# powerblade_5v0.net
KiCad netlist of a schematic drawn in EAGLE
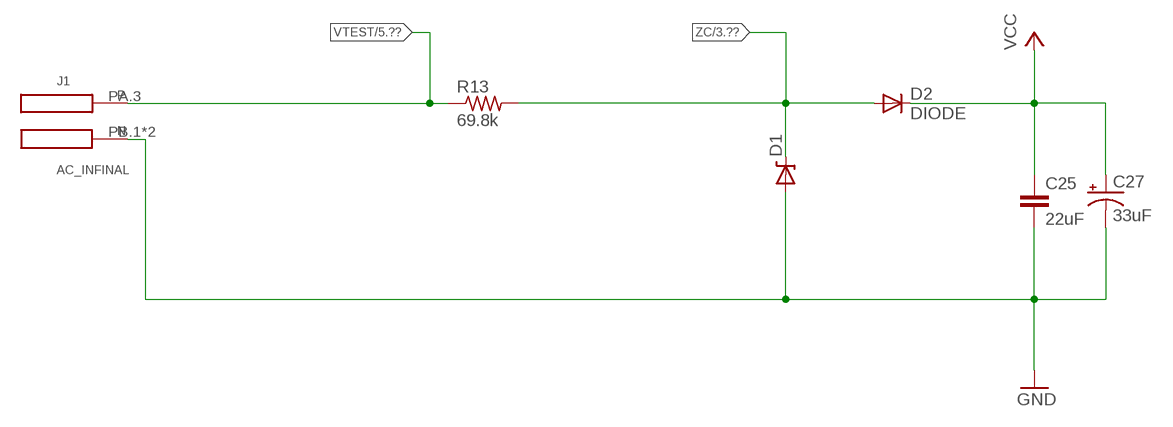
[diagram p0: schematic, sheet 1]
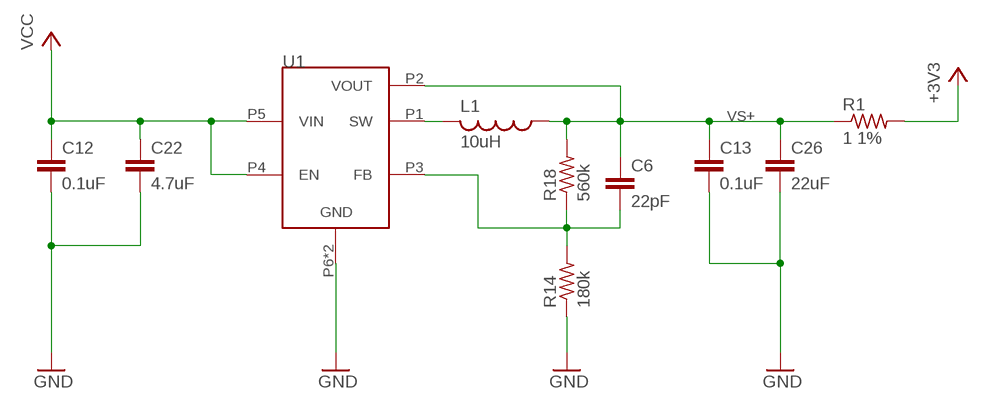
[diagram p1: schematic, sheet 2]
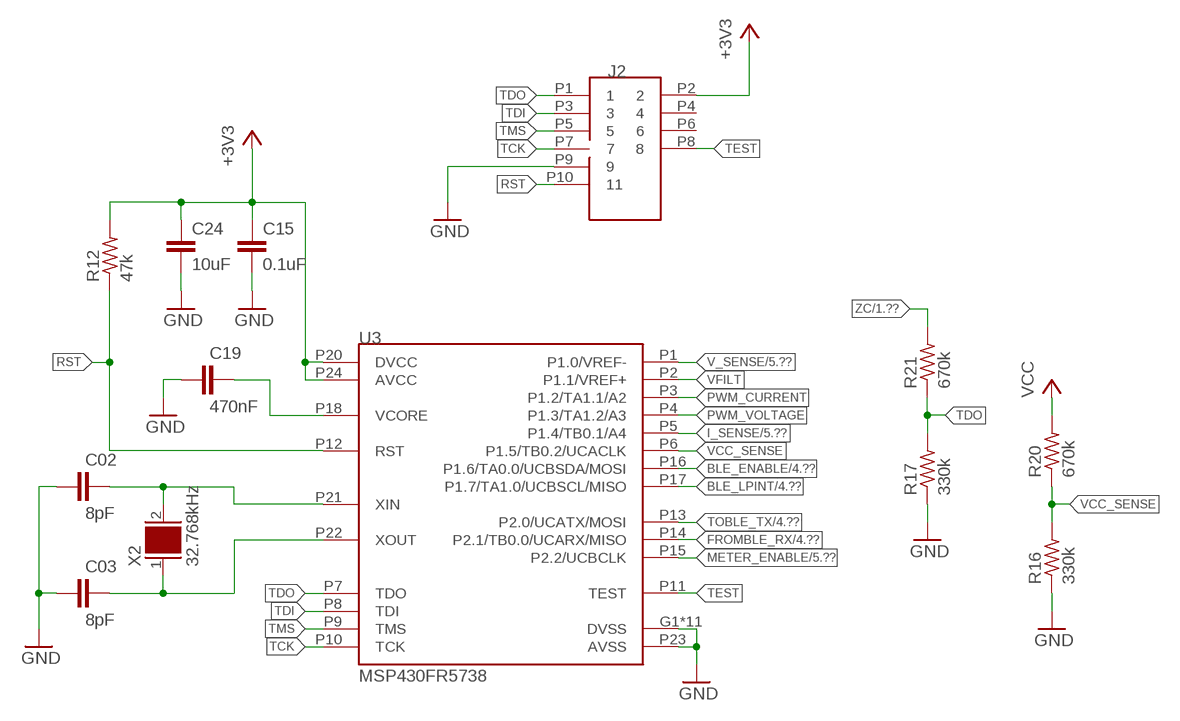
[diagram p2: schematic, sheet 3]
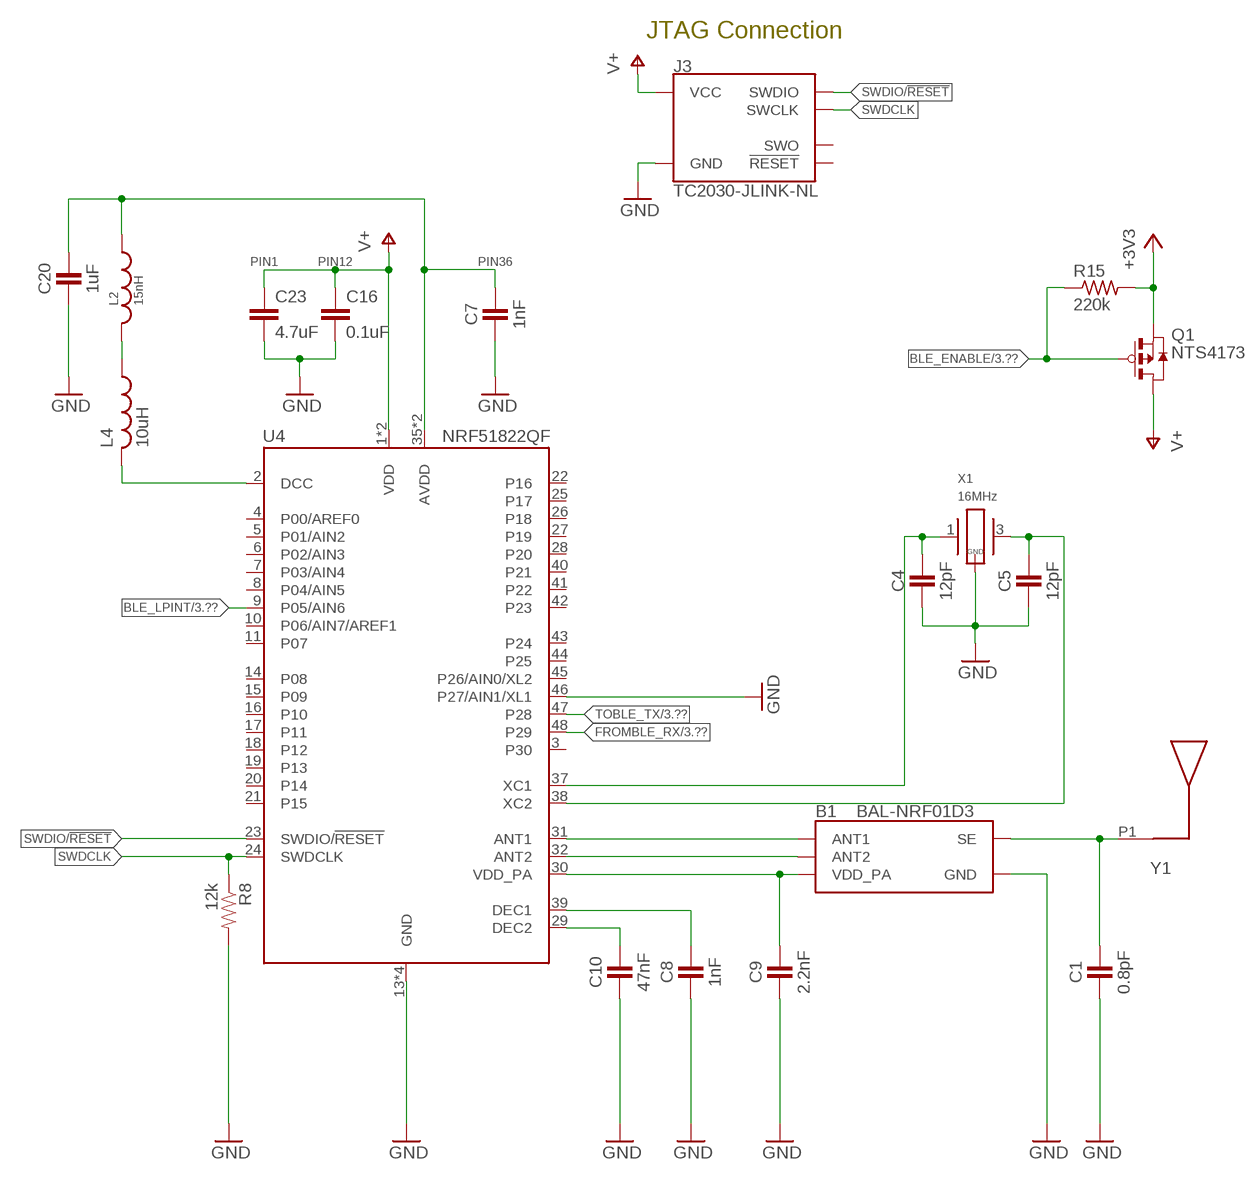
[diagram p3: schematic, sheet 4]
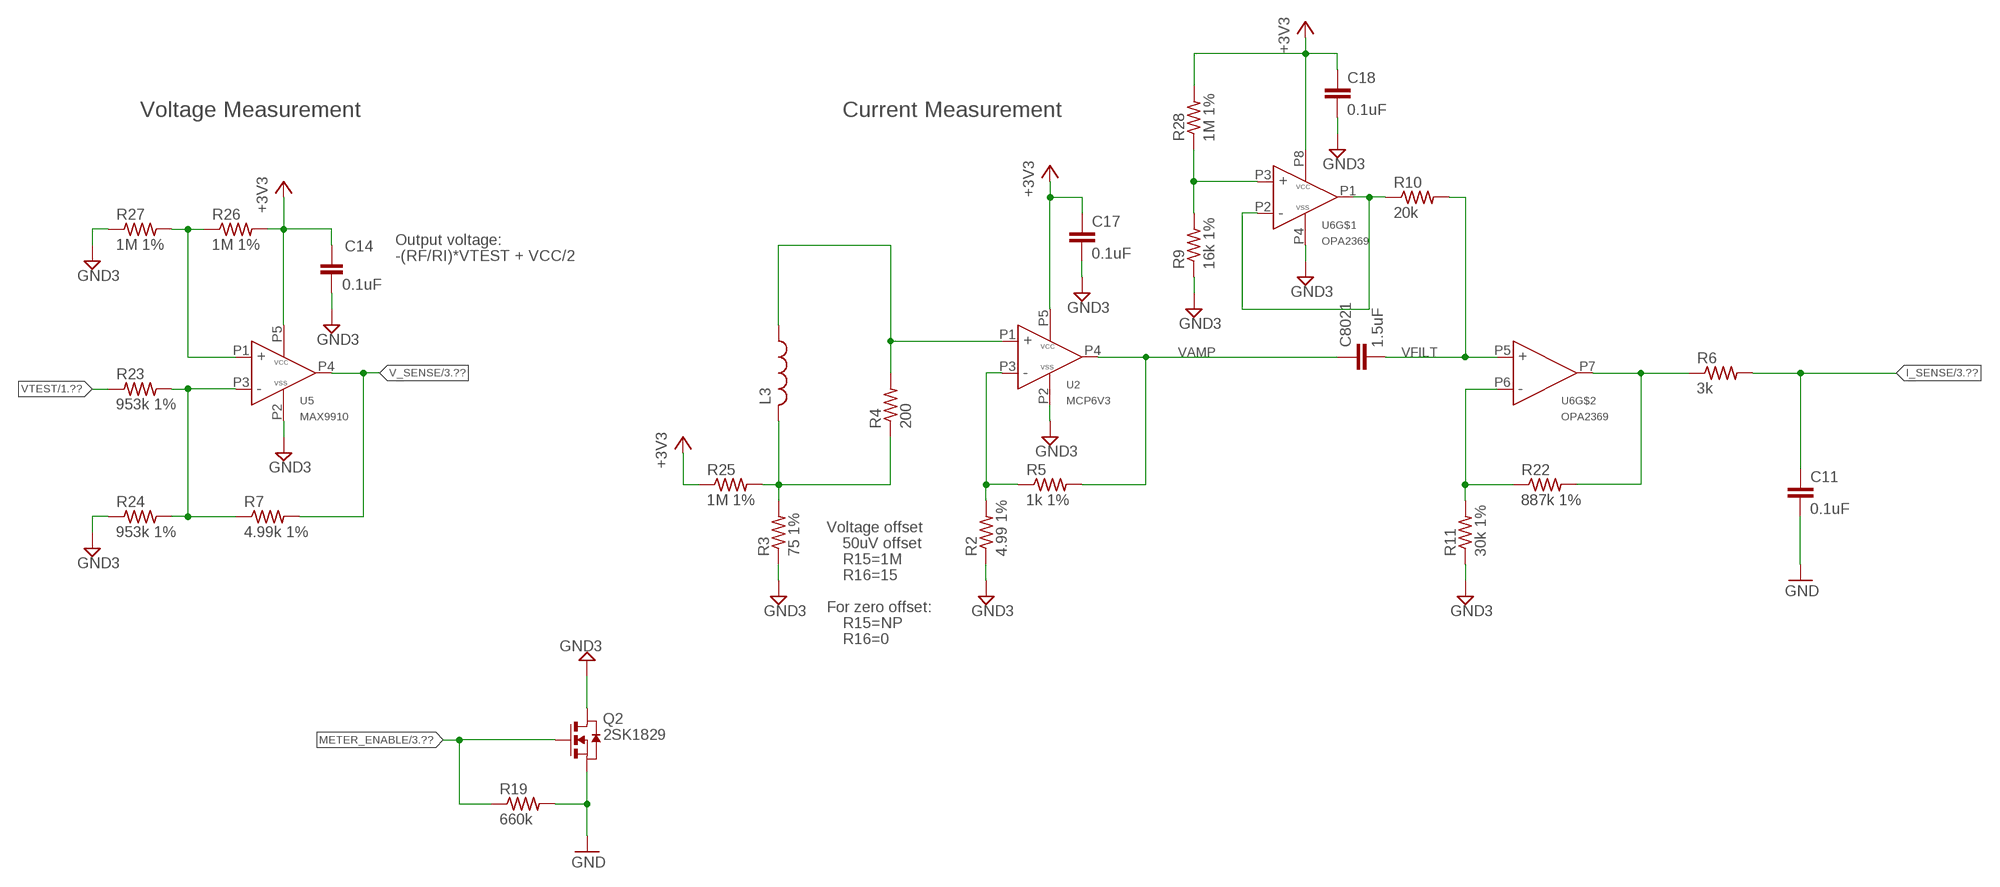
[diagram p4: schematic, sheet 5]

(export (version "E")
  (design (tool "Eeschema 10.0.6"))
  (components
    (comp (ref "C6")
      (value "22pF")
      (footprint "eagle-import:C0402")
      (libsource (lib "eagle-import") (part "C-EUC0402"))
    )
    (comp (ref "C12")
      (value "0.1uF")
      (footprint "eagle-import:C0402")
      (libsource (lib "eagle-import") (part "C-EUC0402"))
    )
    (comp (ref "C13")
      (value "0.1uF")
      (footprint "eagle-import:C0402_SM")
      (libsource (lib "eagle-import") (part "C-EUC0402_SM"))
    )
    (comp (ref "C22")
      (value "4.7uF")
      (footprint "eagle-import:C0402")
      (libsource (lib "eagle-import") (part "C-EUC0402"))
    )
    (comp (ref "C26")
      (value "22uF")
      (footprint "eagle-import:C0603_SM")
      (libsource (lib "eagle-import") (part "C-EUC0603_SM"))
    )
    (comp (ref "L1")
      (value "10uH")
      (footprint "eagle-import:L0805")
      (libsource (lib "eagle-import") (part "L-USL0805"))
    )
    (comp (ref "R1")
      (value "1 1%")
      (footprint "eagle-import:R0603_SM")
      (libsource (lib "eagle-import") (part "R-US_R0603_SM"))
    )
    (comp (ref "R14")
      (value "180k")
      (footprint "eagle-import:R0402")
      (libsource (lib "eagle-import") (part "R-US_R0402"))
    )
    (comp (ref "R18")
      (value "560k")
      (footprint "eagle-import:R0402")
      (libsource (lib "eagle-import") (part "R-US_R0402"))
    )
    (comp (ref "U1")
      (value "TPS62122")
      (footprint "eagle-import:WDFN-6")
      (libsource (lib "eagle-import") (part "TPS62122"))
    )
    (comp (ref "C25")
      (value "22uF")
      (footprint "eagle-import:C0603_SM")
      (libsource (lib "eagle-import") (part "C-EUC0603_SM"))
    )
    (comp (ref "C27")
      (value "33uF")
      (footprint "eagle-import:CPOL0805_SM")
      (libsource (lib "eagle-import") (part "CPOL-US0805_SM"))
    )
    (comp (ref "D1")
      (value "ZENERBZT52")
      (footprint "eagle-import:BZT52")
      (fields (field (name "DIGIKEY") "BZT52C10T-7DICT-ND "))
      (libsource (lib "eagle-import") (part "ZENERBZT52"))
    )
    (comp (ref "D2")
      (value "DIODE")
      (footprint "eagle-import:BAS521")
      (libsource (lib "eagle-import") (part "DIODE"))
    )
    (comp (ref "J1")
      (value "AC_INFINAL")
      (footprint "eagle-import:AC3_FINAL")
      (libsource (lib "eagle-import") (part "AC_INFINAL"))
    )
    (comp (ref "R13")
      (value "69.8k")
      (footprint "eagle-import:R1210")
      (libsource (lib "eagle-import") (part "R-US_R1210"))
    )
    (comp (ref "B1")
      (value "BAL-NRF01D3")
      (footprint "eagle-import:BAL-NRF01D3")
      (libsource (lib "eagle-import") (part "BAL-NRF01D3"))
    )
    (comp (ref "C1")
      (value "0.8pF")
      (footprint "eagle-import:0402_CAP")
      (libsource (lib "eagle-import") (part "CAPACITOR"))
    )
    (comp (ref "C4")
      (value "12pF")
      (footprint "eagle-import:0402_CAP")
      (libsource (lib "eagle-import") (part "CAPACITOR"))
    )
    (comp (ref "C5")
      (value "12pF")
      (footprint "eagle-import:0402_CAP")
      (libsource (lib "eagle-import") (part "CAPACITOR"))
    )
    (comp (ref "C7")
      (value "1nF")
      (footprint "eagle-import:0402_CAP")
      (libsource (lib "eagle-import") (part "CAPACITOR"))
    )
    (comp (ref "C8")
      (value "1nF")
      (footprint "eagle-import:0402_CAP")
      (libsource (lib "eagle-import") (part "CAPACITOR"))
    )
    (comp (ref "C9")
      (value "2.2nF")
      (footprint "eagle-import:0402_CAP")
      (libsource (lib "eagle-import") (part "CAPACITOR"))
    )
    (comp (ref "C10")
      (value "47nF")
      (footprint "eagle-import:0402_CAP")
      (libsource (lib "eagle-import") (part "CAPACITOR"))
    )
    (comp (ref "C16")
      (value "0.1uF")
      (footprint "eagle-import:C0402")
      (libsource (lib "eagle-import") (part "C-EUC0402"))
    )
    (comp (ref "C20")
      (value "1uF")
      (footprint "eagle-import:0402_CAP")
      (libsource (lib "eagle-import") (part "CAPACITOR"))
    )
    (comp (ref "C23")
      (value "4.7uF")
      (footprint "eagle-import:C0402")
      (libsource (lib "eagle-import") (part "C-EUC0402"))
    )
    (comp (ref "J3")
      (value "TC2030-JLINK-NL")
      (footprint "eagle-import:TC2030-IDC-NL")
      (libsource (lib "eagle-import") (part "TC2030-JLINK-NL"))
    )
    (comp (ref "L2")
      (value "15nH")
      (footprint "eagle-import:0402_CAP")
      (libsource (lib "eagle-import") (part "INDUCTOR0402"))
    )
    (comp (ref "L4")
      (value "10uH")
      (footprint "eagle-import:C0603_TN")
      (libsource (lib "eagle-import") (part "L-USL0603_TN"))
    )
    (comp (ref "Q1")
      (value "NTS4173")
      (footprint "eagle-import:SC-70-3")
      (libsource (lib "eagle-import") (part "NTS4173"))
    )
    (comp (ref "R8")
      (value "12k")
      (footprint "eagle-import:0402_RES")
      (libsource (lib "eagle-import") (part "RESISTOR"))
    )
    (comp (ref "R15")
      (value "220k")
      (footprint "eagle-import:R0402_SM")
      (libsource (lib "eagle-import") (part "R-US_R0402_SM"))
    )
    (comp (ref "U4")
      (value "NRF51822QF")
      (footprint "eagle-import:QFN-48-6MM")
      (libsource (lib "eagle-import") (part "NRF51822QF"))
    )
    (comp (ref "X1")
      (value "16MHz")
      (footprint "eagle-import:TXC-8Y")
      (libsource (lib "eagle-import") (part "TXC-8Y"))
    )
    (comp (ref "Y1")
      (value "UREACH_XTEND")
      (footprint "eagle-import:UREACH_XTEND")
      (libsource (lib "eagle-import") (part "UREACH_XTEND"))
    )
    (comp (ref "C11")
      (value "0.1uF")
      (footprint "eagle-import:C0402")
      (libsource (lib "eagle-import") (part "C-EUC0402"))
    )
    (comp (ref "C14")
      (value "0.1uF")
      (footprint "eagle-import:0402_CAP")
      (libsource (lib "eagle-import") (part "CAPACITOR"))
    )
    (comp (ref "C17")
      (value "0.1uF")
      (footprint "eagle-import:C0402")
      (libsource (lib "eagle-import") (part "C-EUC0402"))
    )
    (comp (ref "C18")
      (value "0.1uF")
      (footprint "eagle-import:C0402")
      (libsource (lib "eagle-import") (part "C-EUC0402"))
    )
    (comp (ref "C8021")
      (value "1.5uF")
      (footprint "eagle-import:C0402")
      (libsource (lib "eagle-import") (part "C-EUC0402"))
    )
    (comp (ref "L3")
      (value "L-USL0805")
      (footprint "eagle-import:L0805")
      (libsource (lib "eagle-import") (part "L-USL0805"))
    )
    (comp (ref "Q2")
      (value "2SK1829")
      (footprint "eagle-import:SC-70-3")
      (libsource (lib "eagle-import") (part "2SK1829"))
    )
    (comp (ref "R2")
      (value "4.99 1%")
      (footprint "eagle-import:R0402")
      (libsource (lib "eagle-import") (part "R-US_R0402"))
    )
    (comp (ref "R3")
      (value "75 1%")
      (footprint "eagle-import:R0402")
      (libsource (lib "eagle-import") (part "R-US_R0402"))
    )
    (comp (ref "R4")
      (value "200")
      (footprint "eagle-import:R0402")
      (libsource (lib "eagle-import") (part "R-US_R0402"))
    )
    (comp (ref "R5")
      (value "1k 1%")
      (footprint "eagle-import:R0402")
      (libsource (lib "eagle-import") (part "R-US_R0402"))
    )
    (comp (ref "R6")
      (value "3k")
      (footprint "eagle-import:R0402_SM")
      (libsource (lib "eagle-import") (part "R-US_R0402_SM"))
    )
    (comp (ref "R7")
      (value "4.99k 1%")
      (footprint "eagle-import:R0402")
      (libsource (lib "eagle-import") (part "R-US_R0402"))
    )
    (comp (ref "R9")
      (value "16k 1%")
      (footprint "eagle-import:R0402")
      (libsource (lib "eagle-import") (part "R-US_R0402"))
    )
    (comp (ref "R10")
      (value "20k")
      (footprint "eagle-import:R0402")
      (libsource (lib "eagle-import") (part "R-US_R0402"))
    )
    (comp (ref "R11")
      (value "30k 1%")
      (footprint "eagle-import:R0402")
      (libsource (lib "eagle-import") (part "R-US_R0402"))
    )
    (comp (ref "R19")
      (value "660k")
      (footprint "eagle-import:R0402")
      (libsource (lib "eagle-import") (part "R-US_R0402"))
    )
    (comp (ref "R22")
      (value "887k 1%")
      (footprint "eagle-import:R0402")
      (libsource (lib "eagle-import") (part "R-US_R0402"))
    )
    (comp (ref "R23")
      (value "953k 1%")
      (footprint "eagle-import:R0402")
      (libsource (lib "eagle-import") (part "R-US_R0402"))
    )
    (comp (ref "R24")
      (value "953k 1%")
      (footprint "eagle-import:R0402")
      (libsource (lib "eagle-import") (part "R-US_R0402"))
    )
    (comp (ref "R25")
      (value "1M 1%")
      (footprint "eagle-import:R0402")
      (libsource (lib "eagle-import") (part "R-US_R0402"))
    )
    (comp (ref "R26")
      (value "1M 1%")
      (footprint "eagle-import:R0402")
      (libsource (lib "eagle-import") (part "R-US_R0402"))
    )
    (comp (ref "R27")
      (value "1M 1%")
      (footprint "eagle-import:R0402_SM")
      (libsource (lib "eagle-import") (part "R-US_R0402_SM"))
    )
    (comp (ref "R28")
      (value "1M 1%")
      (footprint "eagle-import:R0402")
      (libsource (lib "eagle-import") (part "R-US_R0402"))
    )
    (comp (ref "U2")
      (value "MCP6V3")
      (footprint "eagle-import:SC70-5")
      (fields (field (name "DIGIKEY") "296-19547-1-ND"))
      (libsource (lib "eagle-import") (part "MCP6V3"))
    )
    (comp (ref "U5")
      (value "MAX9910")
      (footprint "eagle-import:SC70-5")
      (fields (field (name "DIGIKEY") "296-25252-1-ND"))
      (libsource (lib "eagle-import") (part "MAX9910"))
    )
    (comp (ref "U6")
      (value "OPA2369")
      (footprint "eagle-import:SOT-23-8")
      (libsource (lib "eagle-import") (part "OPA2369"))
    )
    (comp (ref "C02")
      (value "8pF")
      (footprint "eagle-import:C0402")
      (libsource (lib "eagle-import") (part "C-EUC0402"))
    )
    (comp (ref "C03")
      (value "8pF")
      (footprint "eagle-import:C0402")
      (libsource (lib "eagle-import") (part "C-EUC0402"))
    )
    (comp (ref "C15")
      (value "0.1uF")
      (footprint "eagle-import:C0402")
      (libsource (lib "eagle-import") (part "C-EUC0402"))
    )
    (comp (ref "C19")
      (value "470nF")
      (footprint "eagle-import:C0402")
      (libsource (lib "eagle-import") (part "C-EUC0402"))
    )
    (comp (ref "C24")
      (value "10uF")
      (footprint "eagle-import:C0603_SM")
      (libsource (lib "eagle-import") (part "C-EUC0603_SM"))
    )
    (comp (ref "J2")
      (value "JTAG_14PIN_IDC-ND")
      (footprint "eagle-import:TC2050-IDC-NL-430-ND")
      (libsource (lib "eagle-import") (part "JTAG_14PIN_IDC-ND"))
    )
    (comp (ref "R12")
      (value "47k")
      (footprint "eagle-import:R0402")
      (libsource (lib "eagle-import") (part "R-US_R0402"))
    )
    (comp (ref "R16")
      (value "330k")
      (footprint "eagle-import:R0402")
      (libsource (lib "eagle-import") (part "R-US_R0402"))
    )
    (comp (ref "R17")
      (value "330k")
      (footprint "eagle-import:R0402")
      (libsource (lib "eagle-import") (part "R-US_R0402"))
    )
    (comp (ref "R20")
      (value "670k")
      (footprint "eagle-import:R0402")
      (libsource (lib "eagle-import") (part "R-US_R0402"))
    )
    (comp (ref "R21")
      (value "670k")
      (footprint "eagle-import:R0402")
      (libsource (lib "eagle-import") (part "R-US_R0402"))
    )
    (comp (ref "U3")
      (value "MSP430FR5738")
      (footprint "eagle-import:VQFN-24")
      (libsource (lib "eagle-import") (part "MSP430FR5738"))
    )
    (comp (ref "X2")
      (value "32.768kHz")
      (footprint "eagle-import:0805")
      (libsource (lib "eagle-import") (part "CRYSTAL_0805"))
    )
  )
  (nets
    (net (code "1") (name "+3V3") (class "Default")
      (node (ref "C14") (pin "1") (pinfunction "1_1") (pintype "bidirectional"))
      (node (ref "C15") (pin "1") (pinfunction "1_1") (pintype "passive"))
      (node (ref "C17") (pin "1") (pinfunction "1_1") (pintype "passive"))
      (node (ref "C18") (pin "1") (pinfunction "1_1") (pintype "passive"))
      (node (ref "C24") (pin "1") (pinfunction "1_1") (pintype "passive"))
      (node (ref "J2") (pin "P2") (pinfunction "2_P2") (pintype "bidirectional"))
      (node (ref "Q1") (pin "P2") (pinfunction "S_P2") (pintype "passive"))
      (node (ref "R1") (pin "2") (pinfunction "2_2") (pintype "passive"))
      (node (ref "R12") (pin "2") (pinfunction "2_2") (pintype "passive"))
      (node (ref "R15") (pin "2") (pinfunction "2_2") (pintype "passive"))
      (node (ref "R25") (pin "1") (pinfunction "1_1") (pintype "passive"))
      (node (ref "R26") (pin "2") (pinfunction "2_2") (pintype "passive"))
      (node (ref "R28") (pin "2") (pinfunction "2_2") (pintype "passive"))
      (node (ref "U2") (pin "P5") (pinfunction "VCC_P5") (pintype "bidirectional"))
      (node (ref "U3") (pin "P20") (pinfunction "DVCC_P20") (pintype "bidirectional"))
      (node (ref "U3") (pin "P24") (pinfunction "AVCC_P24") (pintype "bidirectional"))
      (node (ref "U5") (pin "P5") (pinfunction "VCC_P5") (pintype "bidirectional"))
      (node (ref "U6") (pin "P8") (pinfunction "VCC_P8") (pintype "bidirectional"))
    )
    (net (code "2") (name "BLE_ENABLE") (class "Default")
      (node (ref "Q1") (pin "P1") (pinfunction "G_P1") (pintype "passive"))
      (node (ref "R15") (pin "1") (pinfunction "1_1") (pintype "passive"))
      (node (ref "U3") (pin "P16") (pinfunction "P1.6/TA0.0/UCBSDA/MOSI_P16") (pintype "bidirectional"))
    )
    (net (code "3") (name "BLE_LPINT") (class "Default")
      (node (ref "U3") (pin "P17") (pinfunction "P1.7/TA1.0/UCBSCL/MISO_P17") (pintype "bidirectional"))
      (node (ref "U4") (pin "9") (pinfunction "P05/AIN6_9") (pintype "bidirectional"))
    )
    (net (code "4") (name "FROMBLE_RX") (class "Default")
      (node (ref "U3") (pin "P14") (pinfunction "P2.1/TB0.0/UCARX/MISO_P14") (pintype "bidirectional"))
      (node (ref "U4") (pin "48") (pinfunction "P29_48") (pintype "bidirectional"))
    )
    (net (code "5") (name "GND") (class "Default")
      (node (ref "B1") (pin "GND") (pinfunction "GND_GND") (pintype "bidirectional"))
      (node (ref "C02") (pin "1") (pinfunction "1_1") (pintype "passive"))
      (node (ref "C03") (pin "1") (pinfunction "1_1") (pintype "passive"))
      (node (ref "C1") (pin "2") (pinfunction "2_2") (pintype "bidirectional"))
      (node (ref "C10") (pin "2") (pinfunction "2_2") (pintype "bidirectional"))
      (node (ref "C11") (pin "2") (pinfunction "2_2") (pintype "passive"))
      (node (ref "C12") (pin "2") (pinfunction "2_2") (pintype "passive"))
      (node (ref "C13") (pin "2") (pinfunction "2_2") (pintype "passive"))
      (node (ref "C15") (pin "2") (pinfunction "2_2") (pintype "passive"))
      (node (ref "C16") (pin "2") (pinfunction "2_2") (pintype "passive"))
      (node (ref "C19") (pin "1") (pinfunction "1_1") (pintype "passive"))
      (node (ref "C20") (pin "2") (pinfunction "2_2") (pintype "bidirectional"))
      (node (ref "C22") (pin "2") (pinfunction "2_2") (pintype "passive"))
      (node (ref "C23") (pin "2") (pinfunction "2_2") (pintype "passive"))
      (node (ref "C24") (pin "2") (pinfunction "2_2") (pintype "passive"))
      (node (ref "C25") (pin "2") (pinfunction "2_2") (pintype "passive"))
      (node (ref "C26") (pin "2") (pinfunction "2_2") (pintype "passive"))
      (node (ref "C27") (pin "-") (pinfunction "-_-") (pintype "passive"))
      (node (ref "C4") (pin "2") (pinfunction "2_2") (pintype "bidirectional"))
      (node (ref "C5") (pin "2") (pinfunction "2_2") (pintype "bidirectional"))
      (node (ref "C7") (pin "2") (pinfunction "2_2") (pintype "bidirectional"))
      (node (ref "C8") (pin "2") (pinfunction "2_2") (pintype "bidirectional"))
      (node (ref "C9") (pin "2") (pinfunction "2_2") (pintype "bidirectional"))
      (node (ref "D1") (pin "A") (pinfunction "A_A") (pintype "passive"))
      (node (ref "J1") (pin "PB.1") (pinfunction "N_PB.1") (pintype "bidirectional"))
      (node (ref "J1") (pin "PB.3") (pinfunction "N_PB.3") (pintype "bidirectional"))
      (node (ref "J2") (pin "P9") (pinfunction "9_P9") (pintype "bidirectional"))
      (node (ref "J3") (pin "5") (pinfunction "GND_5") (pintype "bidirectional"))
      (node (ref "Q2") (pin "P2") (pinfunction "S_P2") (pintype "passive"))
      (node (ref "R14") (pin "1") (pinfunction "1_1") (pintype "passive"))
      (node (ref "R16") (pin "1") (pinfunction "1_1") (pintype "passive"))
      (node (ref "R17") (pin "1") (pinfunction "1_1") (pintype "passive"))
      (node (ref "R19") (pin "2") (pinfunction "2_2") (pintype "passive"))
      (node (ref "R8") (pin "2") (pinfunction "2_2") (pintype "passive"))
      (node (ref "U1") (pin "P6") (pinfunction "GND_P6") (pintype "bidirectional"))
      (node (ref "U1") (pin "PAD") (pinfunction "GND_PAD") (pintype "bidirectional"))
      (node (ref "U3") (pin "G1") (pinfunction "DVSS_G1") (pintype "bidirectional"))
      (node (ref "U3") (pin "G2") (pinfunction "DVSS_G2") (pintype "bidirectional"))
      (node (ref "U3") (pin "G3") (pinfunction "DVSS_G3") (pintype "bidirectional"))
      (node (ref "U3") (pin "G4") (pinfunction "DVSS_G4") (pintype "bidirectional"))
      (node (ref "U3") (pin "G5") (pinfunction "DVSS_G5") (pintype "bidirectional"))
      (node (ref "U3") (pin "G6") (pinfunction "DVSS_G6") (pintype "bidirectional"))
      (node (ref "U3") (pin "G7") (pinfunction "DVSS_G7") (pintype "bidirectional"))
      (node (ref "U3") (pin "G8") (pinfunction "DVSS_G8") (pintype "bidirectional"))
      (node (ref "U3") (pin "G9") (pinfunction "DVSS_G9") (pintype "bidirectional"))
      (node (ref "U3") (pin "P19") (pinfunction "DVSS_P19") (pintype "bidirectional"))
      (node (ref "U3") (pin "P23") (pinfunction "AVSS_P23") (pintype "bidirectional"))
      (node (ref "U3") (pin "PAD") (pinfunction "DVSS_PAD") (pintype "bidirectional"))
      (node (ref "U4") (pin "13") (pinfunction "GND_13") (pintype "bidirectional"))
      (node (ref "U4") (pin "33") (pinfunction "GND_33") (pintype "bidirectional"))
      (node (ref "U4") (pin "34") (pinfunction "GND_34") (pintype "bidirectional"))
      (node (ref "U4") (pin "46") (pinfunction "P27/AIN1/XL1_46") (pintype "bidirectional"))
      (node (ref "U4") (pin "GND") (pinfunction "GND_GND") (pintype "bidirectional"))
      (node (ref "X1") (pin "2") (pinfunction "GND_2") (pintype "bidirectional"))
      (node (ref "X1") (pin "4") (pinfunction "GND_4") (pintype "bidirectional"))
    )
    (net (code "6") (name "GND3") (class "Default")
      (node (ref "C14") (pin "2") (pinfunction "2_2") (pintype "bidirectional"))
      (node (ref "C17") (pin "2") (pinfunction "2_2") (pintype "passive"))
      (node (ref "C18") (pin "2") (pinfunction "2_2") (pintype "passive"))
      (node (ref "Q2") (pin "P3") (pinfunction "D_P3") (pintype "passive"))
      (node (ref "R11") (pin "1") (pinfunction "1_1") (pintype "passive"))
      (node (ref "R2") (pin "1") (pinfunction "1_1") (pintype "passive"))
      (node (ref "R24") (pin "1") (pinfunction "1_1") (pintype "passive"))
      (node (ref "R27") (pin "1") (pinfunction "1_1") (pintype "passive"))
      (node (ref "R3") (pin "1") (pinfunction "1_1") (pintype "passive"))
      (node (ref "R9") (pin "1") (pinfunction "1_1") (pintype "passive"))
      (node (ref "U2") (pin "P2") (pinfunction "VSS_P2") (pintype "bidirectional"))
      (node (ref "U5") (pin "P2") (pinfunction "VSS_P2") (pintype "bidirectional"))
      (node (ref "U6") (pin "P4") (pinfunction "VSS_P4") (pintype "bidirectional"))
    )
    (net (code "7") (name "I_SENSE") (class "Default")
      (node (ref "C11") (pin "1") (pinfunction "1_1") (pintype "passive"))
      (node (ref "R6") (pin "2") (pinfunction "2_2") (pintype "passive"))
      (node (ref "U3") (pin "P5") (pinfunction "P1.4/TB0.1/A4_P5") (pintype "bidirectional"))
    )
    (net (code "8") (name "METER_ENABLE") (class "Default")
      (node (ref "Q2") (pin "P1") (pinfunction "G_P1") (pintype "passive"))
      (node (ref "R19") (pin "1") (pinfunction "1_1") (pintype "passive"))
      (node (ref "U3") (pin "P15") (pinfunction "P2.2/UCBCLK_P15") (pintype "bidirectional"))
    )
    (net (code "9") (name "Net-(B1-PadSE)") (class "Default")
      (node (ref "B1") (pin "SE") (pinfunction "SE_SE") (pintype "bidirectional"))
      (node (ref "C1") (pin "1") (pinfunction "1_1") (pintype "bidirectional"))
      (node (ref "Y1") (pin "P1") (pinfunction "P1_P1") (pintype "bidirectional"))
    )
    (net (code "10") (name "Net-(B1-VDD_PA)") (class "Default")
      (node (ref "B1") (pin "VCC") (pinfunction "VDD_PA_VCC") (pintype "bidirectional"))
      (node (ref "C9") (pin "1") (pinfunction "1_1") (pintype "bidirectional"))
      (node (ref "U4") (pin "30") (pinfunction "VDD_PA_30") (pintype "bidirectional"))
    )
    (net (code "11") (name "Net-(C20-Pad1)") (class "Default")
      (node (ref "C20") (pin "1") (pinfunction "1_1") (pintype "bidirectional"))
      (node (ref "C7") (pin "1") (pinfunction "1_1") (pintype "bidirectional"))
      (node (ref "L2") (pin "1") (pinfunction "1_1") (pintype "bidirectional"))
      (node (ref "U4") (pin "35") (pinfunction "AVDD_35") (pintype "bidirectional"))
      (node (ref "U4") (pin "36") (pinfunction "AVDD_36") (pintype "bidirectional"))
    )
    (net (code "12") (name "Net-(L2-Pad2)") (class "Default")
      (node (ref "L2") (pin "2") (pinfunction "2_2") (pintype "bidirectional"))
      (node (ref "L4") (pin "1") (pinfunction "1_1") (pintype "passive"))
    )
    (net (code "13") (name "Net-(L3-Pad2)") (class "Default")
      (node (ref "L3") (pin "2") (pinfunction "2_2") (pintype "passive"))
      (node (ref "R25") (pin "2") (pinfunction "2_2") (pintype "passive"))
      (node (ref "R3") (pin "2") (pinfunction "2_2") (pintype "passive"))
      (node (ref "R4") (pin "1") (pinfunction "1_1") (pintype "passive"))
    )
    (net (code "14") (name "Net-(U1-FB)") (class "Default")
      (node (ref "C6") (pin "2") (pinfunction "2_2") (pintype "passive"))
      (node (ref "R14") (pin "2") (pinfunction "2_2") (pintype "passive"))
      (node (ref "R18") (pin "1") (pinfunction "1_1") (pintype "passive"))
      (node (ref "U1") (pin "P3") (pinfunction "FB_P3") (pintype "bidirectional"))
    )
    (net (code "15") (name "Net-(U1-SW)") (class "Default")
      (node (ref "L1") (pin "2") (pinfunction "2_2") (pintype "passive"))
      (node (ref "U1") (pin "P1") (pinfunction "SW_P1") (pintype "bidirectional"))
    )
    (net (code "16") (name "Net-(U2-IN+)") (class "Default")
      (node (ref "L3") (pin "1") (pinfunction "1_1") (pintype "passive"))
      (node (ref "R4") (pin "2") (pinfunction "2_2") (pintype "passive"))
      (node (ref "U2") (pin "P1") (pinfunction "IN+_P1") (pintype "bidirectional"))
    )
    (net (code "17") (name "Net-(U2-IN-)") (class "Default")
      (node (ref "R2") (pin "2") (pinfunction "2_2") (pintype "passive"))
      (node (ref "R5") (pin "1") (pinfunction "1_1") (pintype "passive"))
      (node (ref "U2") (pin "P3") (pinfunction "IN-_P3") (pintype "bidirectional"))
    )
    (net (code "18") (name "Net-(U3-VCORE)") (class "Default")
      (node (ref "C19") (pin "2") (pinfunction "2_2") (pintype "passive"))
      (node (ref "U3") (pin "P18") (pinfunction "VCORE_P18") (pintype "bidirectional"))
    )
    (net (code "19") (name "Net-(U3-XIN)") (class "Default")
      (node (ref "C02") (pin "2") (pinfunction "2_2") (pintype "passive"))
      (node (ref "U3") (pin "P21") (pinfunction "XIN_P21") (pintype "bidirectional"))
      (node (ref "X2") (pin "2") (pinfunction "P2_2") (pintype "bidirectional"))
    )
    (net (code "20") (name "Net-(U3-XOUT)") (class "Default")
      (node (ref "C03") (pin "2") (pinfunction "2_2") (pintype "passive"))
      (node (ref "U3") (pin "P22") (pinfunction "XOUT_P22") (pintype "bidirectional"))
      (node (ref "X2") (pin "1") (pinfunction "P1_1") (pintype "bidirectional"))
    )
    (net (code "21") (name "Net-(U4-ANT1)") (class "Default")
      (node (ref "B1") (pin "ANT1") (pinfunction "ANT1_ANT1") (pintype "bidirectional"))
      (node (ref "U4") (pin "31") (pinfunction "ANT1_31") (pintype "bidirectional"))
    )
    (net (code "22") (name "Net-(U4-ANT2)") (class "Default")
      (node (ref "B1") (pin "ANT2") (pinfunction "ANT2_ANT2") (pintype "bidirectional"))
      (node (ref "U4") (pin "32") (pinfunction "ANT2_32") (pintype "bidirectional"))
    )
    (net (code "23") (name "Net-(U4-DCC)") (class "Default")
      (node (ref "L4") (pin "2") (pinfunction "2_2") (pintype "passive"))
      (node (ref "U4") (pin "2") (pinfunction "DCC_2") (pintype "bidirectional"))
    )
    (net (code "24") (name "Net-(U4-DEC1)") (class "Default")
      (node (ref "C8") (pin "1") (pinfunction "1_1") (pintype "bidirectional"))
      (node (ref "U4") (pin "39") (pinfunction "DEC1_39") (pintype "bidirectional"))
    )
    (net (code "25") (name "Net-(U4-DEC2)") (class "Default")
      (node (ref "C10") (pin "1") (pinfunction "1_1") (pintype "bidirectional"))
      (node (ref "U4") (pin "29") (pinfunction "DEC2_29") (pintype "bidirectional"))
    )
    (net (code "26") (name "Net-(U4-XC1)") (class "Default")
      (node (ref "C4") (pin "1") (pinfunction "1_1") (pintype "bidirectional"))
      (node (ref "U4") (pin "37") (pinfunction "XC1_37") (pintype "bidirectional"))
      (node (ref "X1") (pin "1") (pinfunction "1_1") (pintype "bidirectional"))
    )
    (net (code "27") (name "Net-(U4-XC2)") (class "Default")
      (node (ref "C5") (pin "1") (pinfunction "1_1") (pintype "bidirectional"))
      (node (ref "U4") (pin "38") (pinfunction "XC2_38") (pintype "bidirectional"))
      (node (ref "X1") (pin "3") (pinfunction "2_3") (pintype "bidirectional"))
    )
    (net (code "28") (name "Net-(U5-IN+)") (class "Default")
      (node (ref "R26") (pin "1") (pinfunction "1_1") (pintype "passive"))
      (node (ref "R27") (pin "2") (pinfunction "2_2") (pintype "passive"))
      (node (ref "U5") (pin "P1") (pinfunction "IN+_P1") (pintype "bidirectional"))
    )
    (net (code "29") (name "Net-(U5-IN-)") (class "Default")
      (node (ref "R23") (pin "2") (pinfunction "2_2") (pintype "passive"))
      (node (ref "R24") (pin "2") (pinfunction "2_2") (pintype "passive"))
      (node (ref "R7") (pin "1") (pinfunction "1_1") (pintype "passive"))
      (node (ref "U5") (pin "P3") (pinfunction "IN-_P3") (pintype "bidirectional"))
    )
    (net (code "30") (name "Net-(U6A-IN+)") (class "Default")
      (node (ref "R28") (pin "1") (pinfunction "1_1") (pintype "passive"))
      (node (ref "R9") (pin "2") (pinfunction "2_2") (pintype "passive"))
      (node (ref "U6") (pin "P3") (pinfunction "IN+_P3") (pintype "bidirectional"))
    )
    (net (code "31") (name "Net-(U6A-IN-)") (class "Default")
      (node (ref "R10") (pin "1") (pinfunction "1_1") (pintype "passive"))
      (node (ref "U6") (pin "P1") (pinfunction "OUT_P1") (pintype "bidirectional"))
      (node (ref "U6") (pin "P2") (pinfunction "IN-_P2") (pintype "bidirectional"))
    )
    (net (code "32") (name "Net-(U6B-IN-)") (class "Default")
      (node (ref "R11") (pin "2") (pinfunction "2_2") (pintype "passive"))
      (node (ref "R22") (pin "1") (pinfunction "1_1") (pintype "passive"))
      (node (ref "U6") (pin "P6") (pinfunction "IN-_P6") (pintype "bidirectional"))
    )
    (net (code "33") (name "Net-(U6B-OUT)") (class "Default")
      (node (ref "R22") (pin "2") (pinfunction "2_2") (pintype "passive"))
      (node (ref "R6") (pin "1") (pinfunction "1_1") (pintype "passive"))
      (node (ref "U6") (pin "P7") (pinfunction "OUT_P7") (pintype "bidirectional"))
    )
    (net (code "34") (name "PWM_CURRENT") (class "Default")
      (node (ref "U3") (pin "P3") (pinfunction "P1.2/TA1.1/A2_P3") (pintype "bidirectional"))
    )
    (net (code "35") (name "PWM_VOLTAGE") (class "Default")
      (node (ref "U3") (pin "P4") (pinfunction "P1.3/TA1.2/A3_P4") (pintype "bidirectional"))
    )
    (net (code "36") (name "RST") (class "Default")
      (node (ref "J2") (pin "P10") (pinfunction "11_P10") (pintype "bidirectional"))
      (node (ref "R12") (pin "1") (pinfunction "1_1") (pintype "passive"))
      (node (ref "U3") (pin "P12") (pinfunction "RST_P12") (pintype "bidirectional"))
    )
    (net (code "37") (name "SWDCLK") (class "Default")
      (node (ref "J3") (pin "4") (pinfunction "SWCLK_4") (pintype "bidirectional"))
      (node (ref "R8") (pin "1") (pinfunction "1_1") (pintype "passive"))
      (node (ref "U4") (pin "24") (pinfunction "SWDCLK_24") (pintype "bidirectional"))
    )
    (net (code "38") (name "SWDIO{slash}~{RESET}") (class "Default")
      (node (ref "J3") (pin "2") (pinfunction "SWDIO_2") (pintype "bidirectional"))
      (node (ref "U4") (pin "23") (pinfunction "SWDIO/~{RESET}_23") (pintype "bidirectional"))
    )
    (net (code "39") (name "TCK") (class "Default")
      (node (ref "J2") (pin "P7") (pinfunction "7_P7") (pintype "bidirectional"))
      (node (ref "U3") (pin "P10") (pinfunction "TCK_P10") (pintype "bidirectional"))
    )
    (net (code "40") (name "TDI") (class "Default")
      (node (ref "J2") (pin "P3") (pinfunction "3_P3") (pintype "bidirectional"))
      (node (ref "U3") (pin "P8") (pinfunction "TDI_P8") (pintype "bidirectional"))
    )
    (net (code "41") (name "TDO") (class "Default")
      (node (ref "J2") (pin "P1") (pinfunction "1_P1") (pintype "bidirectional"))
      (node (ref "R17") (pin "2") (pinfunction "2_2") (pintype "passive"))
      (node (ref "R21") (pin "1") (pinfunction "1_1") (pintype "passive"))
      (node (ref "U3") (pin "P7") (pinfunction "TDO_P7") (pintype "bidirectional"))
    )
    (net (code "42") (name "TEST") (class "Default")
      (node (ref "J2") (pin "P8") (pinfunction "8_P8") (pintype "bidirectional"))
      (node (ref "U3") (pin "P11") (pinfunction "TEST_P11") (pintype "bidirectional"))
    )
    (net (code "43") (name "TMS") (class "Default")
      (node (ref "J2") (pin "P5") (pinfunction "5_P5") (pintype "bidirectional"))
      (node (ref "U3") (pin "P9") (pinfunction "TMS_P9") (pintype "bidirectional"))
    )
    (net (code "44") (name "TOBLE_TX") (class "Default")
      (node (ref "U3") (pin "P13") (pinfunction "P2.0/UCATX/MOSI_P13") (pintype "bidirectional"))
      (node (ref "U4") (pin "47") (pinfunction "P28_47") (pintype "bidirectional"))
    )
    (net (code "45") (name "V+") (class "Default")
      (node (ref "C16") (pin "1") (pinfunction "1_1") (pintype "passive"))
      (node (ref "C23") (pin "1") (pinfunction "1_1") (pintype "passive"))
      (node (ref "J3") (pin "1") (pinfunction "VCC_1") (pintype "bidirectional"))
      (node (ref "Q1") (pin "P3") (pinfunction "D_P3") (pintype "passive"))
      (node (ref "U4") (pin "1") (pinfunction "VDD_1") (pintype "bidirectional"))
      (node (ref "U4") (pin "12") (pinfunction "VDD_12") (pintype "bidirectional"))
    )
    (net (code "46") (name "VAMP") (class "Default")
      (node (ref "C8021") (pin "1") (pinfunction "1_1") (pintype "passive"))
      (node (ref "R5") (pin "2") (pinfunction "2_2") (pintype "passive"))
      (node (ref "U2") (pin "P4") (pinfunction "OUT_P4") (pintype "bidirectional"))
    )
    (net (code "47") (name "VCC") (class "Default")
      (node (ref "C12") (pin "1") (pinfunction "1_1") (pintype "passive"))
      (node (ref "C22") (pin "1") (pinfunction "1_1") (pintype "passive"))
      (node (ref "C25") (pin "1") (pinfunction "1_1") (pintype "passive"))
      (node (ref "C27") (pin "+") (pinfunction "+_+") (pintype "passive"))
      (node (ref "D2") (pin "C") (pinfunction "C_C") (pintype "passive"))
      (node (ref "R20") (pin "2") (pinfunction "2_2") (pintype "passive"))
      (node (ref "U1") (pin "P4") (pinfunction "EN_P4") (pintype "bidirectional"))
      (node (ref "U1") (pin "P5") (pinfunction "VIN_P5") (pintype "bidirectional"))
    )
    (net (code "48") (name "VCC_SENSE") (class "Default")
      (node (ref "R16") (pin "2") (pinfunction "2_2") (pintype "passive"))
      (node (ref "R20") (pin "1") (pinfunction "1_1") (pintype "passive"))
      (node (ref "U3") (pin "P6") (pinfunction "P1.5/TB0.2/UCACLK_P6") (pintype "bidirectional"))
    )
    (net (code "49") (name "VFILT") (class "Default")
      (node (ref "C8021") (pin "2") (pinfunction "2_2") (pintype "passive"))
      (node (ref "R10") (pin "2") (pinfunction "2_2") (pintype "passive"))
      (node (ref "U3") (pin "P2") (pinfunction "P1.1/VREF+_P2") (pintype "bidirectional"))
      (node (ref "U6") (pin "P5") (pinfunction "IN+_P5") (pintype "bidirectional"))
    )
    (net (code "50") (name "VS+") (class "Default")
      (node (ref "C13") (pin "1") (pinfunction "1_1") (pintype "passive"))
      (node (ref "C26") (pin "1") (pinfunction "1_1") (pintype "passive"))
      (node (ref "C6") (pin "1") (pinfunction "1_1") (pintype "passive"))
      (node (ref "L1") (pin "1") (pinfunction "1_1") (pintype "passive"))
      (node (ref "R1") (pin "1") (pinfunction "1_1") (pintype "passive"))
      (node (ref "R18") (pin "2") (pinfunction "2_2") (pintype "passive"))
      (node (ref "U1") (pin "P2") (pinfunction "VOUT_P2") (pintype "bidirectional"))
    )
    (net (code "51") (name "VTEST") (class "Default")
      (node (ref "J1") (pin "PA.3") (pinfunction "P_PA.3") (pintype "bidirectional"))
      (node (ref "R13") (pin "1") (pinfunction "1_1") (pintype "passive"))
      (node (ref "R23") (pin "1") (pinfunction "1_1") (pintype "passive"))
    )
    (net (code "52") (name "V_SENSE") (class "Default")
      (node (ref "R7") (pin "2") (pinfunction "2_2") (pintype "passive"))
      (node (ref "U3") (pin "P1") (pinfunction "P1.0/VREF-_P1") (pintype "bidirectional"))
      (node (ref "U5") (pin "P4") (pinfunction "OUT_P4") (pintype "bidirectional"))
    )
    (net (code "53") (name "ZC") (class "Default")
      (node (ref "D1") (pin "C") (pinfunction "C_C") (pintype "passive"))
      (node (ref "D2") (pin "A") (pinfunction "A_A") (pintype "passive"))
      (node (ref "R13") (pin "2") (pinfunction "2_2") (pintype "passive"))
      (node (ref "R21") (pin "2") (pinfunction "2_2") (pintype "passive"))
    )
    (net (code "54") (name "unconnected-(J2-4-PadP4)") (class "Default")
      (node (ref "J2") (pin "P4") (pinfunction "4_P4") (pintype "bidirectional"))
    )
    (net (code "55") (name "unconnected-(J2-6-PadP6)") (class "Default")
      (node (ref "J2") (pin "P6") (pinfunction "6_P6") (pintype "bidirectional"))
    )
    (net (code "56") (name "unconnected-(J3-SWO-Pad6)") (class "Default")
      (node (ref "J3") (pin "6") (pinfunction "SWO_6") (pintype "bidirectional"))
    )
    (net (code "57") (name "unconnected-(J3-~{RESET}-Pad3)") (class "Default")
      (node (ref "J3") (pin "3") (pinfunction "~{RESET}_3") (pintype "bidirectional"))
    )
    (net (code "58") (name "unconnected-(U4-P00{slash}AREF0-Pad4)") (class "Default")
      (node (ref "U4") (pin "4") (pinfunction "P00/AREF0_4") (pintype "bidirectional"))
    )
    (net (code "59") (name "unconnected-(U4-P01{slash}AIN2-Pad5)") (class "Default")
      (node (ref "U4") (pin "5") (pinfunction "P01/AIN2_5") (pintype "bidirectional"))
    )
    (net (code "60") (name "unconnected-(U4-P02{slash}AIN3-Pad6)") (class "Default")
      (node (ref "U4") (pin "6") (pinfunction "P02/AIN3_6") (pintype "bidirectional"))
    )
    (net (code "61") (name "unconnected-(U4-P03{slash}AIN4-Pad7)") (class "Default")
      (node (ref "U4") (pin "7") (pinfunction "P03/AIN4_7") (pintype "bidirectional"))
    )
    (net (code "62") (name "unconnected-(U4-P04{slash}AIN5-Pad8)") (class "Default")
      (node (ref "U4") (pin "8") (pinfunction "P04/AIN5_8") (pintype "bidirectional"))
    )
    (net (code "63") (name "unconnected-(U4-P06{slash}AIN7{slash}AREF1-Pad10)") (class "Default")
      (node (ref "U4") (pin "10") (pinfunction "P06/AIN7/AREF1_10") (pintype "bidirectional"))
    )
    (net (code "64") (name "unconnected-(U4-P07-Pad11)") (class "Default")
      (node (ref "U4") (pin "11") (pinfunction "P07_11") (pintype "bidirectional"))
    )
    (net (code "65") (name "unconnected-(U4-P08-Pad14)") (class "Default")
      (node (ref "U4") (pin "14") (pinfunction "P08_14") (pintype "bidirectional"))
    )
    (net (code "66") (name "unconnected-(U4-P09-Pad15)") (class "Default")
      (node (ref "U4") (pin "15") (pinfunction "P09_15") (pintype "bidirectional"))
    )
    (net (code "67") (name "unconnected-(U4-P10-Pad16)") (class "Default")
      (node (ref "U4") (pin "16") (pinfunction "P10_16") (pintype "bidirectional"))
    )
    (net (code "68") (name "unconnected-(U4-P11-Pad17)") (class "Default")
      (node (ref "U4") (pin "17") (pinfunction "P11_17") (pintype "bidirectional"))
    )
    (net (code "69") (name "unconnected-(U4-P12-Pad18)") (class "Default")
      (node (ref "U4") (pin "18") (pinfunction "P12_18") (pintype "bidirectional"))
    )
    (net (code "70") (name "unconnected-(U4-P13-Pad19)") (class "Default")
      (node (ref "U4") (pin "19") (pinfunction "P13_19") (pintype "bidirectional"))
    )
    (net (code "71") (name "unconnected-(U4-P14-Pad20)") (class "Default")
      (node (ref "U4") (pin "20") (pinfunction "P14_20") (pintype "bidirectional"))
    )
    (net (code "72") (name "unconnected-(U4-P15-Pad21)") (class "Default")
      (node (ref "U4") (pin "21") (pinfunction "P15_21") (pintype "bidirectional"))
    )
    (net (code "73") (name "unconnected-(U4-P16-Pad22)") (class "Default")
      (node (ref "U4") (pin "22") (pinfunction "P16_22") (pintype "bidirectional"))
    )
    (net (code "74") (name "unconnected-(U4-P17-Pad25)") (class "Default")
      (node (ref "U4") (pin "25") (pinfunction "P17_25") (pintype "bidirectional"))
    )
    (net (code "75") (name "unconnected-(U4-P18-Pad26)") (class "Default")
      (node (ref "U4") (pin "26") (pinfunction "P18_26") (pintype "bidirectional"))
    )
    (net (code "76") (name "unconnected-(U4-P19-Pad27)") (class "Default")
      (node (ref "U4") (pin "27") (pinfunction "P19_27") (pintype "bidirectional"))
    )
    (net (code "77") (name "unconnected-(U4-P20-Pad28)") (class "Default")
      (node (ref "U4") (pin "28") (pinfunction "P20_28") (pintype "bidirectional"))
    )
    (net (code "78") (name "unconnected-(U4-P21-Pad40)") (class "Default")
      (node (ref "U4") (pin "40") (pinfunction "P21_40") (pintype "bidirectional"))
    )
    (net (code "79") (name "unconnected-(U4-P22-Pad41)") (class "Default")
      (node (ref "U4") (pin "41") (pinfunction "P22_41") (pintype "bidirectional"))
    )
    (net (code "80") (name "unconnected-(U4-P23-Pad42)") (class "Default")
      (node (ref "U4") (pin "42") (pinfunction "P23_42") (pintype "bidirectional"))
    )
    (net (code "81") (name "unconnected-(U4-P24-Pad43)") (class "Default")
      (node (ref "U4") (pin "43") (pinfunction "P24_43") (pintype "bidirectional"))
    )
    (net (code "82") (name "unconnected-(U4-P25-Pad44)") (class "Default")
      (node (ref "U4") (pin "44") (pinfunction "P25_44") (pintype "bidirectional"))
    )
    (net (code "83") (name "unconnected-(U4-P26{slash}AIN0{slash}XL2-Pad45)") (class "Default")
      (node (ref "U4") (pin "45") (pinfunction "P26/AIN0/XL2_45") (pintype "bidirectional"))
    )
    (net (code "84") (name "unconnected-(U4-P30-Pad3)") (class "Default")
      (node (ref "U4") (pin "3") (pinfunction "P30_3") (pintype "bidirectional"))
    )
  )
)
